# ESP32K40.net
KiCad netlist of a schematic drawn in EAGLE
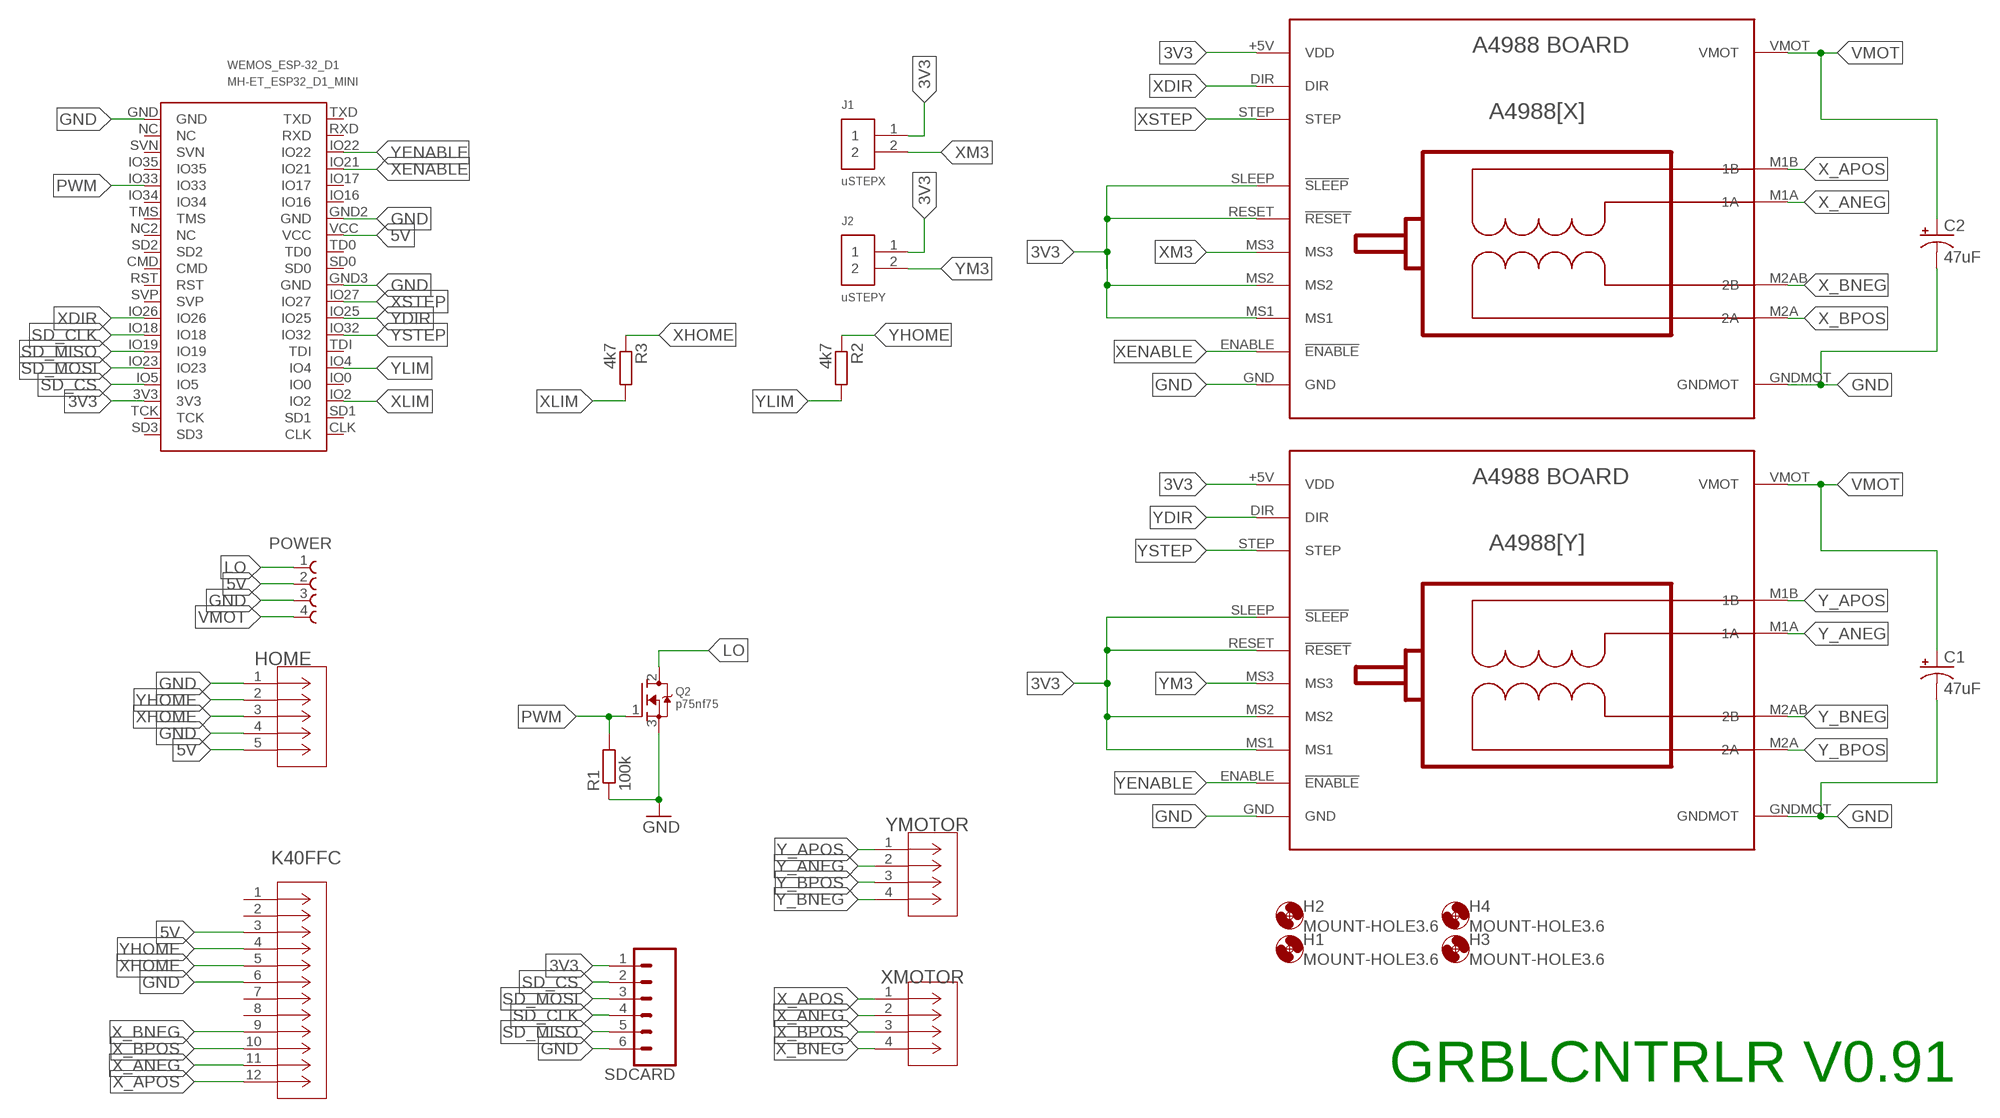
[diagram p0: schematic, sheet 1]

(export (version "E")
  (design (tool "Eeschema 10.0.6"))
  (components
    (comp (ref "A4988[X]")
      (value "XMOTOR")
      (footprint "eagle-import:BOARD_A4988")
      (libsource (lib "eagle-import") (part "BOARD_A4988"))
    )
    (comp (ref "A4988[Y]")
      (value "YMOTOR")
      (footprint "eagle-import:BOARD_A4988")
      (libsource (lib "eagle-import") (part "BOARD_A4988"))
    )
    (comp (ref "C1")
      (value "47uF")
      (footprint "eagle-import:TAP5-70")
      (libsource (lib "eagle-import") (part "CPOL-USTAP5-70"))
    )
    (comp (ref "C2")
      (value "47uF")
      (footprint "eagle-import:TAP5-70")
      (libsource (lib "eagle-import") (part "CPOL-USTAP5-70"))
    )
    (comp (ref "H1")
      (value "MOUNT-HOLE3.6")
      (footprint "eagle-import:3,6")
      (libsource (lib "eagle-import") (part "MOUNT-HOLE3.6"))
    )
    (comp (ref "H2")
      (value "MOUNT-HOLE3.6")
      (footprint "eagle-import:3,6")
      (libsource (lib "eagle-import") (part "MOUNT-HOLE3.6"))
    )
    (comp (ref "H3")
      (value "MOUNT-HOLE3.6")
      (footprint "eagle-import:3,6")
      (libsource (lib "eagle-import") (part "MOUNT-HOLE3.6"))
    )
    (comp (ref "H4")
      (value "MOUNT-HOLE3.6")
      (footprint "eagle-import:3,6")
      (libsource (lib "eagle-import") (part "MOUNT-HOLE3.6"))
    )
    (comp (ref "HOME")
      (value "B5B-XH-A(LF)(SN)")
      (footprint "eagle-import:CONN_B5B-XH-A(LF)(SN)_JST")
      (fields (field (name "COPYRIGHT") "Copyright (C) 2018 Accelerated Designs. All rights reserved"))
      (libsource (lib "eagle-import") (part "B5B-XH-A(LF)(SN)"))
    )
    (comp (ref "J1")
      (value "uSTEPX")
      (footprint "eagle-import:61300211121")
      (fields
        (field (name "DIGI_KEY_PART_NUMBER") "732-5315-ND")
        (field (name "MANUFACTURER") "Wurth Electronics Inc.")
        (field (name "MPN") "61300211121")
        (field (name "CREATED_BY") "PCBLayout.com")
      )
      (libsource (lib "eagle-import") (part "61300211121"))
    )
    (comp (ref "J2")
      (value "uSTEPY")
      (footprint "eagle-import:61300211121")
      (fields
        (field (name "DIGI_KEY_PART_NUMBER") "732-5315-ND")
        (field (name "MANUFACTURER") "Wurth Electronics Inc.")
        (field (name "MPN") "61300211121")
        (field (name "CREATED_BY") "PCBLayout.com")
      )
      (libsource (lib "eagle-import") (part "61300211121"))
    )
    (comp (ref "K40FFC")
      (value "1-84534-2")
      (footprint "eagle-import:CON12_TH_FCC-FPC2")
      (fields (field (name "COPYRIGHT") "Copyright (C) 2016 Accelerated Designs. All rights reserved"))
      (libsource (lib "eagle-import") (part "1-84534-2"))
    )
    (comp (ref "POWER")
      (value "691371700004B")
      (footprint "eagle-import:691371700004B")
      (libsource (lib "eagle-import") (part "691371700004B"))
    )
    (comp (ref "Q2")
      (value "p75nf75")
      (footprint "eagle-import:TO220V")
      (libsource (lib "eagle-import") (part "MOSFET-NGDS_TO220V"))
    )
    (comp (ref "R1")
      (value "100k")
      (footprint "eagle-import:V234_12")
      (libsource (lib "eagle-import") (part "R-EU_V234/12"))
    )
    (comp (ref "R2")
      (value "4k7")
      (footprint "eagle-import:V234_12")
      (libsource (lib "eagle-import") (part "resistor_348_R-EU_V234/12"))
    )
    (comp (ref "R3")
      (value "4k7")
      (footprint "eagle-import:V234_12")
      (libsource (lib "eagle-import") (part "resistor_348_R-EU_V234/12"))
    )
    (comp (ref "SDCARD")
      (value "CONN_06LONGPADS")
      (footprint "eagle-import:1X06_LONGPADS")
      (libsource (lib "eagle-import") (part "CONN_06LONGPADS"))
    )
    (comp (ref "WEMOS_ESP-32_D1")
      (value "MH-ET_ESP32_D1_MINI")
      (footprint "eagle-import:MH-ET_ESP32_D1_MINI")
      (libsource (lib "eagle-import") (part "MH-ET_ESP32_D1_MINI"))
    )
    (comp (ref "XMOTOR")
      (value "B4B-XH-A_(LF)(SN)")
      (footprint "eagle-import:CONN_B4B-XH-A_(LF)(SN)_JST")
      (fields
        (field (name "MANUFACTURER_PART_NUMBER") "B4B-XH-A (LF)(SN)")
        (field (name "COPYRIGHT") "Copyright (C) 2018 Accelerated Designs. All rights reserved")
      )
      (libsource (lib "eagle-import") (part "B4B-XH-A_(LF)(SN)"))
    )
    (comp (ref "YMOTOR")
      (value "B4B-XH-A_(LF)(SN)")
      (footprint "eagle-import:CONN_B4B-XH-A_(LF)(SN)_JST")
      (fields
        (field (name "MANUFACTURER_PART_NUMBER") "B4B-XH-A (LF)(SN)")
        (field (name "COPYRIGHT") "Copyright (C) 2018 Accelerated Designs. All rights reserved")
      )
      (libsource (lib "eagle-import") (part "B4B-XH-A_(LF)(SN)"))
    )
  )
  (nets
    (net (code "1") (name "3V3") (class "Default")
      (node (ref "A4988[X]") (pin "+5V") (pinfunction "VDD_+5V") (pintype "power_in"))
      (node (ref "A4988[X]") (pin "MS1") (pinfunction "MS1_MS1") (pintype "input"))
      (node (ref "A4988[X]") (pin "MS2") (pinfunction "MS2_MS2") (pintype "input"))
      (node (ref "A4988[X]") (pin "RESET") (pinfunction "~{RESET}_RESET") (pintype "input"))
      (node (ref "A4988[X]") (pin "SLEEP") (pinfunction "~{SLEEP}_SLEEP") (pintype "input"))
      (node (ref "A4988[Y]") (pin "+5V") (pinfunction "VDD_+5V") (pintype "power_in"))
      (node (ref "A4988[Y]") (pin "MS1") (pinfunction "MS1_MS1") (pintype "input"))
      (node (ref "A4988[Y]") (pin "MS2") (pinfunction "MS2_MS2") (pintype "input"))
      (node (ref "A4988[Y]") (pin "RESET") (pinfunction "~{RESET}_RESET") (pintype "input"))
      (node (ref "A4988[Y]") (pin "SLEEP") (pinfunction "~{SLEEP}_SLEEP") (pintype "input"))
      (node (ref "J1") (pin "1") (pinfunction "1_1") (pintype "passive"))
      (node (ref "J2") (pin "1") (pinfunction "1_1") (pintype "passive"))
      (node (ref "SDCARD") (pin "1") (pinfunction "1_1") (pintype "passive"))
      (node (ref "WEMOS_ESP-32_D1") (pin "3V3") (pinfunction "3V3_3V3") (pintype "bidirectional"))
    )
    (net (code "2") (name "5V") (class "Default")
      (node (ref "HOME") (pin "5") (pinfunction "5_5") (pintype "passive"))
      (node (ref "K40FFC") (pin "3") (pinfunction "3_3") (pintype "passive"))
      (node (ref "POWER") (pin "2") (pinfunction "2_2") (pintype "passive"))
      (node (ref "WEMOS_ESP-32_D1") (pin "VCC") (pinfunction "VCC_VCC") (pintype "bidirectional"))
    )
    (net (code "3") (name "GND") (class "Default")
      (node (ref "A4988[X]") (pin "GND") (pinfunction "GND_GND") (pintype "power_in"))
      (node (ref "A4988[X]") (pin "GNDMOT") (pinfunction "GNDMOT_GNDMOT") (pintype "power_in"))
      (node (ref "A4988[Y]") (pin "GND") (pinfunction "GND_GND") (pintype "power_in"))
      (node (ref "A4988[Y]") (pin "GNDMOT") (pinfunction "GNDMOT_GNDMOT") (pintype "power_in"))
      (node (ref "C1") (pin "-") (pinfunction "-_-") (pintype "passive"))
      (node (ref "C2") (pin "-") (pinfunction "-_-") (pintype "passive"))
      (node (ref "HOME") (pin "1") (pinfunction "1_1") (pintype "passive"))
      (node (ref "HOME") (pin "4") (pinfunction "4_4") (pintype "passive"))
      (node (ref "K40FFC") (pin "6") (pinfunction "6_6") (pintype "passive"))
      (node (ref "POWER") (pin "3") (pinfunction "3_3") (pintype "passive"))
      (node (ref "Q2") (pin "3") (pinfunction "S_3") (pintype "bidirectional"))
      (node (ref "R1") (pin "1") (pinfunction "1_1") (pintype "passive"))
      (node (ref "SDCARD") (pin "6") (pinfunction "6_6") (pintype "passive"))
      (node (ref "WEMOS_ESP-32_D1") (pin "GND") (pinfunction "GND_GND") (pintype "bidirectional"))
      (node (ref "WEMOS_ESP-32_D1") (pin "GND2") (pinfunction "GND_GND2") (pintype "bidirectional"))
      (node (ref "WEMOS_ESP-32_D1") (pin "GND3") (pinfunction "GND_GND3") (pintype "bidirectional"))
    )
    (net (code "4") (name "LO") (class "Default")
      (node (ref "POWER") (pin "1") (pinfunction "1_1") (pintype "passive"))
      (node (ref "Q2") (pin "2") (pinfunction "D_2") (pintype "bidirectional"))
    )
    (net (code "5") (name "PWM") (class "Default")
      (node (ref "Q2") (pin "1") (pinfunction "G_1") (pintype "bidirectional"))
      (node (ref "R1") (pin "2") (pinfunction "2_2") (pintype "passive"))
      (node (ref "WEMOS_ESP-32_D1") (pin "IO33") (pinfunction "IO33_IO33") (pintype "bidirectional"))
    )
    (net (code "6") (name "SD_CLK") (class "Default")
      (node (ref "SDCARD") (pin "4") (pinfunction "4_4") (pintype "passive"))
      (node (ref "WEMOS_ESP-32_D1") (pin "IO18") (pinfunction "IO18_IO18") (pintype "bidirectional"))
    )
    (net (code "7") (name "SD_CS") (class "Default")
      (node (ref "SDCARD") (pin "2") (pinfunction "2_2") (pintype "passive"))
      (node (ref "WEMOS_ESP-32_D1") (pin "IO5") (pinfunction "IO5_IO5") (pintype "bidirectional"))
    )
    (net (code "8") (name "SD_MISO") (class "Default")
      (node (ref "SDCARD") (pin "5") (pinfunction "5_5") (pintype "passive"))
      (node (ref "WEMOS_ESP-32_D1") (pin "IO19") (pinfunction "IO19_IO19") (pintype "bidirectional"))
    )
    (net (code "9") (name "SD_MOSI") (class "Default")
      (node (ref "SDCARD") (pin "3") (pinfunction "3_3") (pintype "passive"))
      (node (ref "WEMOS_ESP-32_D1") (pin "IO23") (pinfunction "IO23_IO23") (pintype "bidirectional"))
    )
    (net (code "10") (name "VMOT") (class "Default")
      (node (ref "A4988[X]") (pin "VMOT") (pinfunction "VMOT_VMOT") (pintype "power_in"))
      (node (ref "A4988[Y]") (pin "VMOT") (pinfunction "VMOT_VMOT") (pintype "power_in"))
      (node (ref "C1") (pin "+") (pinfunction "+_+") (pintype "passive"))
      (node (ref "C2") (pin "+") (pinfunction "+_+") (pintype "passive"))
      (node (ref "POWER") (pin "4") (pinfunction "4_4") (pintype "passive"))
    )
    (net (code "11") (name "XDIR") (class "Default")
      (node (ref "A4988[X]") (pin "DIR") (pinfunction "DIR_DIR") (pintype "input"))
      (node (ref "WEMOS_ESP-32_D1") (pin "IO26") (pinfunction "IO26_IO26") (pintype "bidirectional"))
    )
    (net (code "12") (name "XENABLE") (class "Default")
      (node (ref "A4988[X]") (pin "ENABLE") (pinfunction "~{ENABLE}_ENABLE") (pintype "input"))
      (node (ref "WEMOS_ESP-32_D1") (pin "IO21") (pinfunction "IO21_IO21") (pintype "bidirectional"))
    )
    (net (code "13") (name "XHOME") (class "Default")
      (node (ref "HOME") (pin "3") (pinfunction "3_3") (pintype "passive"))
      (node (ref "K40FFC") (pin "5") (pinfunction "5_5") (pintype "passive"))
      (node (ref "R3") (pin "1") (pinfunction "1_1") (pintype "passive"))
    )
    (net (code "14") (name "XLIM") (class "Default")
      (node (ref "R3") (pin "2") (pinfunction "2_2") (pintype "passive"))
      (node (ref "WEMOS_ESP-32_D1") (pin "IO2") (pinfunction "IO2_IO2") (pintype "bidirectional"))
    )
    (net (code "15") (name "XM3") (class "Default")
      (node (ref "A4988[X]") (pin "MS3") (pinfunction "MS3_MS3") (pintype "input"))
      (node (ref "J1") (pin "2") (pinfunction "2_2") (pintype "passive"))
    )
    (net (code "16") (name "XSTEP") (class "Default")
      (node (ref "A4988[X]") (pin "STEP") (pinfunction "STEP_STEP") (pintype "input"))
      (node (ref "WEMOS_ESP-32_D1") (pin "IO27") (pinfunction "IO27_IO27") (pintype "bidirectional"))
    )
    (net (code "17") (name "X_ANEG") (class "Default")
      (node (ref "A4988[X]") (pin "M1A") (pinfunction "1A_M1A") (pintype "output"))
      (node (ref "K40FFC") (pin "11") (pinfunction "11_11") (pintype "passive"))
      (node (ref "XMOTOR") (pin "2") (pinfunction "2_2") (pintype "passive"))
    )
    (net (code "18") (name "X_APOS") (class "Default")
      (node (ref "A4988[X]") (pin "M1B") (pinfunction "1B_M1B") (pintype "output"))
      (node (ref "K40FFC") (pin "12") (pinfunction "12_12") (pintype "passive"))
      (node (ref "XMOTOR") (pin "1") (pinfunction "1_1") (pintype "passive"))
    )
    (net (code "19") (name "X_BNEG") (class "Default")
      (node (ref "A4988[X]") (pin "M2AB") (pinfunction "2B_M2AB") (pintype "output"))
      (node (ref "K40FFC") (pin "9") (pinfunction "9_9") (pintype "passive"))
      (node (ref "XMOTOR") (pin "4") (pinfunction "4_4") (pintype "passive"))
    )
    (net (code "20") (name "X_BPOS") (class "Default")
      (node (ref "A4988[X]") (pin "M2A") (pinfunction "2A_M2A") (pintype "output"))
      (node (ref "K40FFC") (pin "10") (pinfunction "10_10") (pintype "passive"))
      (node (ref "XMOTOR") (pin "3") (pinfunction "3_3") (pintype "passive"))
    )
    (net (code "21") (name "YDIR") (class "Default")
      (node (ref "A4988[Y]") (pin "DIR") (pinfunction "DIR_DIR") (pintype "input"))
      (node (ref "WEMOS_ESP-32_D1") (pin "IO25") (pinfunction "IO25_IO25") (pintype "bidirectional"))
    )
    (net (code "22") (name "YENABLE") (class "Default")
      (node (ref "A4988[Y]") (pin "ENABLE") (pinfunction "~{ENABLE}_ENABLE") (pintype "input"))
      (node (ref "WEMOS_ESP-32_D1") (pin "IO22") (pinfunction "IO22_IO22") (pintype "bidirectional"))
    )
    (net (code "23") (name "YHOME") (class "Default")
      (node (ref "HOME") (pin "2") (pinfunction "2_2") (pintype "passive"))
      (node (ref "K40FFC") (pin "4") (pinfunction "4_4") (pintype "passive"))
      (node (ref "R2") (pin "1") (pinfunction "1_1") (pintype "passive"))
    )
    (net (code "24") (name "YLIM") (class "Default")
      (node (ref "R2") (pin "2") (pinfunction "2_2") (pintype "passive"))
      (node (ref "WEMOS_ESP-32_D1") (pin "IO4") (pinfunction "IO4_IO4") (pintype "bidirectional"))
    )
    (net (code "25") (name "YM3") (class "Default")
      (node (ref "A4988[Y]") (pin "MS3") (pinfunction "MS3_MS3") (pintype "input"))
      (node (ref "J2") (pin "2") (pinfunction "2_2") (pintype "passive"))
    )
    (net (code "26") (name "YSTEP") (class "Default")
      (node (ref "A4988[Y]") (pin "STEP") (pinfunction "STEP_STEP") (pintype "input"))
      (node (ref "WEMOS_ESP-32_D1") (pin "IO32") (pinfunction "IO32_IO32") (pintype "bidirectional"))
    )
    (net (code "27") (name "Y_ANEG") (class "Default")
      (node (ref "A4988[Y]") (pin "M1A") (pinfunction "1A_M1A") (pintype "output"))
      (node (ref "YMOTOR") (pin "2") (pinfunction "2_2") (pintype "passive"))
    )
    (net (code "28") (name "Y_APOS") (class "Default")
      (node (ref "A4988[Y]") (pin "M1B") (pinfunction "1B_M1B") (pintype "output"))
      (node (ref "YMOTOR") (pin "1") (pinfunction "1_1") (pintype "passive"))
    )
    (net (code "29") (name "Y_BNEG") (class "Default")
      (node (ref "A4988[Y]") (pin "M2AB") (pinfunction "2B_M2AB") (pintype "output"))
      (node (ref "YMOTOR") (pin "4") (pinfunction "4_4") (pintype "passive"))
    )
    (net (code "30") (name "Y_BPOS") (class "Default")
      (node (ref "A4988[Y]") (pin "M2A") (pinfunction "2A_M2A") (pintype "output"))
      (node (ref "YMOTOR") (pin "3") (pinfunction "3_3") (pintype "passive"))
    )
    (net (code "31") (name "unconnected-(K40FFC-Pad1)") (class "Default")
      (node (ref "K40FFC") (pin "1") (pinfunction "1_1") (pintype "passive"))
    )
    (net (code "32") (name "unconnected-(K40FFC-Pad2)") (class "Default")
      (node (ref "K40FFC") (pin "2") (pinfunction "2_2") (pintype "passive"))
    )
    (net (code "33") (name "unconnected-(K40FFC-Pad7)") (class "Default")
      (node (ref "K40FFC") (pin "7") (pinfunction "7_7") (pintype "passive"))
    )
    (net (code "34") (name "unconnected-(K40FFC-Pad8)") (class "Default")
      (node (ref "K40FFC") (pin "8") (pinfunction "8_8") (pintype "passive"))
    )
    (net (code "35") (name "unconnected-(WEMOS_ESP-32_D1-NC-PadNC2)") (class "Default")
      (node (ref "WEMOS_ESP-32_D1") (pin "NC2") (pinfunction "NC_NC2") (pintype "bidirectional"))
    )
    (net (code "36") (name "unconnected-(WEMOS_ESP-32_D1-PadCLK)") (class "Default")
      (node (ref "WEMOS_ESP-32_D1") (pin "CLK") (pinfunction "CLK_CLK") (pintype "bidirectional"))
    )
    (net (code "37") (name "unconnected-(WEMOS_ESP-32_D1-PadCMD)") (class "Default")
      (node (ref "WEMOS_ESP-32_D1") (pin "CMD") (pinfunction "CMD_CMD") (pintype "bidirectional"))
    )
    (net (code "38") (name "unconnected-(WEMOS_ESP-32_D1-PadIO0)") (class "Default")
      (node (ref "WEMOS_ESP-32_D1") (pin "IO0") (pinfunction "IO0_IO0") (pintype "bidirectional"))
    )
    (net (code "39") (name "unconnected-(WEMOS_ESP-32_D1-PadIO16)") (class "Default")
      (node (ref "WEMOS_ESP-32_D1") (pin "IO16") (pinfunction "IO16_IO16") (pintype "bidirectional"))
    )
    (net (code "40") (name "unconnected-(WEMOS_ESP-32_D1-PadIO17)") (class "Default")
      (node (ref "WEMOS_ESP-32_D1") (pin "IO17") (pinfunction "IO17_IO17") (pintype "bidirectional"))
    )
    (net (code "41") (name "unconnected-(WEMOS_ESP-32_D1-PadIO34)") (class "Default")
      (node (ref "WEMOS_ESP-32_D1") (pin "IO34") (pinfunction "IO34_IO34") (pintype "bidirectional"))
    )
    (net (code "42") (name "unconnected-(WEMOS_ESP-32_D1-PadIO35)") (class "Default")
      (node (ref "WEMOS_ESP-32_D1") (pin "IO35") (pinfunction "IO35_IO35") (pintype "bidirectional"))
    )
    (net (code "43") (name "unconnected-(WEMOS_ESP-32_D1-PadNC)") (class "Default")
      (node (ref "WEMOS_ESP-32_D1") (pin "NC") (pinfunction "NC_NC") (pintype "bidirectional"))
    )
    (net (code "44") (name "unconnected-(WEMOS_ESP-32_D1-PadRST)") (class "Default")
      (node (ref "WEMOS_ESP-32_D1") (pin "RST") (pinfunction "RST_RST") (pintype "bidirectional"))
    )
    (net (code "45") (name "unconnected-(WEMOS_ESP-32_D1-PadRXD)") (class "Default")
      (node (ref "WEMOS_ESP-32_D1") (pin "RXD") (pinfunction "RXD_RXD") (pintype "bidirectional"))
    )
    (net (code "46") (name "unconnected-(WEMOS_ESP-32_D1-PadSD0)") (class "Default")
      (node (ref "WEMOS_ESP-32_D1") (pin "SD0") (pinfunction "SD0_SD0") (pintype "bidirectional"))
    )
    (net (code "47") (name "unconnected-(WEMOS_ESP-32_D1-PadSD1)") (class "Default")
      (node (ref "WEMOS_ESP-32_D1") (pin "SD1") (pinfunction "SD1_SD1") (pintype "bidirectional"))
    )
    (net (code "48") (name "unconnected-(WEMOS_ESP-32_D1-PadSD2)") (class "Default")
      (node (ref "WEMOS_ESP-32_D1") (pin "SD2") (pinfunction "SD2_SD2") (pintype "bidirectional"))
    )
    (net (code "49") (name "unconnected-(WEMOS_ESP-32_D1-PadSD3)") (class "Default")
      (node (ref "WEMOS_ESP-32_D1") (pin "SD3") (pinfunction "SD3_SD3") (pintype "bidirectional"))
    )
    (net (code "50") (name "unconnected-(WEMOS_ESP-32_D1-PadSVN)") (class "Default")
      (node (ref "WEMOS_ESP-32_D1") (pin "SVN") (pinfunction "SVN_SVN") (pintype "bidirectional"))
    )
    (net (code "51") (name "unconnected-(WEMOS_ESP-32_D1-PadSVP)") (class "Default")
      (node (ref "WEMOS_ESP-32_D1") (pin "SVP") (pinfunction "SVP_SVP") (pintype "bidirectional"))
    )
    (net (code "52") (name "unconnected-(WEMOS_ESP-32_D1-PadTCK)") (class "Default")
      (node (ref "WEMOS_ESP-32_D1") (pin "TCK") (pinfunction "TCK_TCK") (pintype "bidirectional"))
    )
    (net (code "53") (name "unconnected-(WEMOS_ESP-32_D1-PadTD0)") (class "Default")
      (node (ref "WEMOS_ESP-32_D1") (pin "TD0") (pinfunction "TD0_TD0") (pintype "bidirectional"))
    )
    (net (code "54") (name "unconnected-(WEMOS_ESP-32_D1-PadTDI)") (class "Default")
      (node (ref "WEMOS_ESP-32_D1") (pin "TDI") (pinfunction "TDI_TDI") (pintype "bidirectional"))
    )
    (net (code "55") (name "unconnected-(WEMOS_ESP-32_D1-PadTMS)") (class "Default")
      (node (ref "WEMOS_ESP-32_D1") (pin "TMS") (pinfunction "TMS_TMS") (pintype "bidirectional"))
    )
    (net (code "56") (name "unconnected-(WEMOS_ESP-32_D1-PadTXD)") (class "Default")
      (node (ref "WEMOS_ESP-32_D1") (pin "TXD") (pinfunction "TXD_TXD") (pintype "bidirectional"))
    )
  )
)
